# Breeze2_Power_V1.net
KiCad netlist of a schematic drawn in Altium Designer
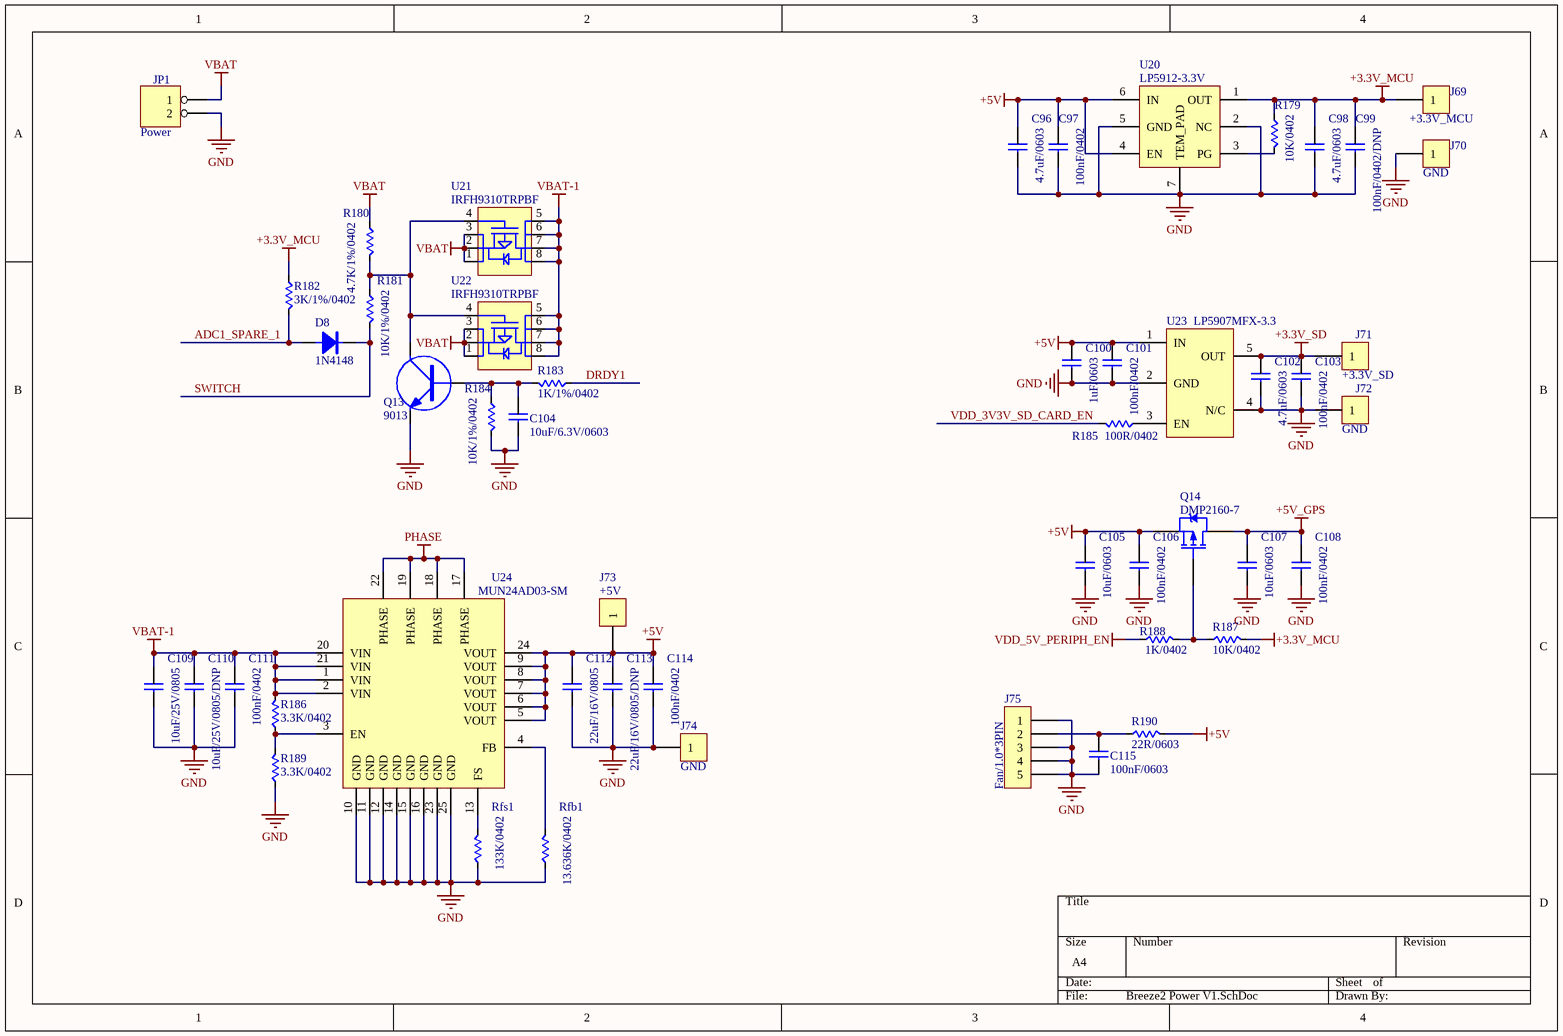
[diagram p0: Breeze2 Power V1.SchDoc]

(export (version "E")
  (design (tool "Eeschema 10.0.6"))
  (components
    (comp (ref "C96")
      (value "4.7uF/0603")
      (footprint "0603C-S")
      (description "CAP")
      (libsource (lib "YUNEEC-SCH") (part "CAP"))
    )
    (comp (ref "C97")
      (value "100nF/0402")
      (footprint "0402C-S")
      (description "CAP")
      (libsource (lib "YUNEEC-SCH") (part "CAP"))
    )
    (comp (ref "C98")
      (value "4.7uF/0603")
      (footprint "0603C-S")
      (description "CAP")
      (libsource (lib "YUNEEC-SCH") (part "CAP"))
    )
    (comp (ref "C99")
      (value "100nF/0402/DNP")
      (footprint "0402C-S")
      (description "CAP")
      (libsource (lib "YUNEEC-SCH") (part "CAP"))
    )
    (comp (ref "C100")
      (value "1uF/0603")
      (footprint "0603C-S")
      (description "CAP")
      (libsource (lib "YUNEEC-SCH") (part "CAP"))
    )
    (comp (ref "C101")
      (value "100nF/0402")
      (footprint "0402C-S")
      (description "CAP")
      (libsource (lib "YUNEEC-SCH") (part "CAP"))
    )
    (comp (ref "C102")
      (value "4.7uF/0603")
      (footprint "0603C-S")
      (description "CAP")
      (libsource (lib "YUNEEC-SCH") (part "CAP"))
    )
    (comp (ref "C103")
      (value "100nF/0402")
      (footprint "0402C-S")
      (description "CAP")
      (libsource (lib "YUNEEC-SCH") (part "CAP"))
    )
    (comp (ref "C104")
      (value "10uF/6.3V/0603")
      (footprint "0603C-S")
      (description "CAP")
      (libsource (lib "YUNEEC-SCH") (part "CAP"))
    )
    (comp (ref "C105")
      (value "10uF/0603")
      (footprint "0603C-S")
      (description "CAP")
      (libsource (lib "YUNEEC-SCH") (part "CAP"))
    )
    (comp (ref "C106")
      (value "100nF/0402")
      (footprint "0402C-S")
      (description "CAP")
      (libsource (lib "YUNEEC-SCH") (part "CAP"))
    )
    (comp (ref "C107")
      (value "10uF/0603")
      (footprint "0603C-S")
      (description "CAP")
      (libsource (lib "YUNEEC-SCH") (part "CAP"))
    )
    (comp (ref "C108")
      (value "100nF/0402")
      (footprint "0402C-S")
      (description "CAP")
      (libsource (lib "YUNEEC-SCH") (part "CAP"))
    )
    (comp (ref "C109")
      (value "10uF/25V/0805")
      (footprint "0805C-S")
      (description "CAP")
      (libsource (lib "YUNEEC-SCH") (part "CAP"))
    )
    (comp (ref "C110")
      (value "10uF/25V/0805/DNP")
      (footprint "0805C-S")
      (description "CAP")
      (libsource (lib "YUNEEC-SCH") (part "CAP"))
    )
    (comp (ref "C111")
      (value "100nF/0402")
      (footprint "0402C-S")
      (description "CAP")
      (libsource (lib "YUNEEC-SCH") (part "CAP"))
    )
    (comp (ref "C112")
      (value "22uF/16V/0805")
      (footprint "0805C-S")
      (description "CAP")
      (libsource (lib "YUNEEC-SCH") (part "CAP"))
    )
    (comp (ref "C113")
      (value "22uF/16V/0805/DNP")
      (footprint "0805C-S")
      (description "CAP")
      (libsource (lib "YUNEEC-SCH") (part "CAP"))
    )
    (comp (ref "C114")
      (value "100nF/0402")
      (footprint "0402C-S")
      (description "CAP")
      (libsource (lib "YUNEEC-SCH") (part "CAP"))
    )
    (comp (ref "C115")
      (value "100nF/0603")
      (footprint "0603C-S")
      (description "CAP")
      (libsource (lib "YUNEEC-SCH") (part "CAP"))
    )
    (comp (ref "D8")
      (value "1N4148")
      (footprint "0603D")
      (description "Diode")
      (libsource (lib "YUNEEC-SCH") (part "DIODE"))
    )
    (comp (ref "J69")
      (value "+3.3V_MCU")
      (footprint "TPJ1.0")
      (description "Connector")
      (libsource (lib "*") (part "CON1"))
    )
    (comp (ref "J70")
      (value "GND")
      (footprint "TPJ1.0")
      (description "Connector")
      (libsource (lib "YUNEEC SCH") (part "CON1"))
    )
    (comp (ref "J71")
      (value "+3.3V_SD")
      (footprint "TPJ1.0")
      (description "Connector")
      (libsource (lib "YUNEEC SCH") (part "CON1"))
    )
    (comp (ref "J72")
      (value "GND")
      (footprint "TPJ1.0")
      (description "Connector")
      (libsource (lib "YUNEEC SCH") (part "CON1"))
    )
    (comp (ref "J73")
      (value "+5V")
      (footprint "TPJ1.3")
      (description "Connector")
      (libsource (lib "") (part "CON1_1"))
    )
    (comp (ref "J74")
      (value "GND")
      (footprint "TPJ1.3")
      (description "Connector")
      (libsource (lib "YUNEEC SCH") (part "CON1"))
    )
    (comp (ref "J75")
      (value "Fan/1.0*3PIN")
      (footprint "1.0*3PIN/SMD-H")
      (description "Connector")
      (libsource (lib "YUNEEC-SCH") (part "CON5"))
    )
    (comp (ref "JP1") (value "Power") (footprint "EC2") (libsource (lib "*") (part "HEADER 2")))
    (comp (ref "Q13")
      (value "9013")
      (footprint "SOT-23A")
      (description "NPN Transistor")
      (libsource (lib "YUNEEC-SCH") (part "NPN"))
    )
    (comp (ref "Q14")
      (value "DMP2160-7")
      (footprint "SOT-23A")
      (description "HEXFET Power MOSFET")
      (libsource (lib "*") (part "IRLML6302"))
    )
    (comp (ref "R179") (value "10K/0402") (footprint "0402R-S") (libsource (lib "YUNEEC-SCH") (part "RES")))
    (comp (ref "R180")
      (value "4.7K/1%/0402")
      (footprint "0402R-S")
      (libsource (lib "YUNEEC-SCH") (part "RES"))
    )
    (comp (ref "R181")
      (value "10K/1%/0402")
      (footprint "0402R-S")
      (libsource (lib "YUNEEC-SCH") (part "RES"))
    )
    (comp (ref "R182") (value "3K/1%/0402") (footprint "0402R-S") (libsource (lib "YUNEEC-SCH") (part "RES")))
    (comp (ref "R183") (value "1K/1%/0402") (footprint "0402R-S") (libsource (lib "YUNEEC-SCH") (part "RES")))
    (comp (ref "R184")
      (value "10K/1%/0402")
      (footprint "0402R-S")
      (libsource (lib "YUNEEC-SCH") (part "RES"))
    )
    (comp (ref "R185") (value "100R/0402") (footprint "0402R-S") (libsource (lib "YUNEEC-SCH") (part "RES")))
    (comp (ref "R186")
      (value "3.3K/0402")
      (footprint "0402R-S")
      (description "Y02-00493")
      (libsource (lib "YUNEEC-SCH") (part "RES"))
    )
    (comp (ref "R187") (value "10K/0402") (footprint "0402R-S") (libsource (lib "YUNEEC-SCH") (part "RES")))
    (comp (ref "R188") (value "1K/0402") (footprint "0402R-S") (libsource (lib "YUNEEC-SCH") (part "RES")))
    (comp (ref "R189")
      (value "3.3K/0402")
      (footprint "0402R-S")
      (description "Y02-00493")
      (libsource (lib "YUNEEC-SCH") (part "RES"))
    )
    (comp (ref "R190") (value "22R/0603") (footprint "0603R-S") (libsource (lib "YUNEEC-SCH") (part "RES")))
    (comp (ref "Rfb1")
      (value "13.636K/0402")
      (footprint "0402R-S")
      (description "Y02-00493")
      (libsource (lib "YUNEEC-SCH") (part "RES"))
    )
    (comp (ref "Rfs1")
      (value "133K/0402")
      (footprint "0402R-S")
      (description "Y02-00493")
      (libsource (lib "YUNEEC-SCH") (part "RES"))
    )
    (comp (ref "U20")
      (value "LP5912-3.3V")
      (footprint "S-PWSON-N6")
      (libsource (lib "YUNEEC-SCH") (part "LP5912-3.3V"))
    )
    (comp (ref "U21")
      (value "IRFH9310TRPBF")
      (footprint "PQFN-8")
      (description "TPCC8104")
      (libsource (lib "YUNEEC-SCH") (part "TPCC8104"))
    )
    (comp (ref "U22")
      (value "IRFH9310TRPBF")
      (footprint "PQFN-8")
      (description "TPCC8104")
      (libsource (lib "YUNEEC-SCH") (part "TPCC8104"))
    )
    (comp (ref "U23")
      (value "LP5907MFX-3.3")
      (footprint "SOT-25A")
      (libsource (lib "YUNEEC-SCH") (part "LP5907"))
    )
    (comp (ref "U24")
      (value "MUN24AD03-SM")
      (footprint "MUN24AD03-SM")
      (libsource (lib "YUNEEC-SCH") (part "MUN24AD03-SM"))
    )
  )
  (nets
    (net (code "1") (name "+3.3V_MCU") (class "Default")
      (node (ref "C98") (pin "1") (pinfunction "1_1") (pintype "passive"))
      (node (ref "C99") (pin "1") (pinfunction "1_1") (pintype "passive"))
      (node (ref "J69") (pin "1") (pinfunction "1_1") (pintype "passive"))
      (node (ref "R179") (pin "1") (pinfunction "1_1") (pintype "passive"))
      (node (ref "R182") (pin "1") (pinfunction "1_1") (pintype "passive"))
      (node (ref "R187") (pin "2") (pinfunction "2_2") (pintype "passive"))
      (node (ref "U20") (pin "1") (pinfunction "OUT_1") (pintype "passive"))
    )
    (net (code "2") (name "+3.3V_SD") (class "Default")
      (node (ref "C102") (pin "1") (pinfunction "1_1") (pintype "passive"))
      (node (ref "C103") (pin "1") (pinfunction "1_1") (pintype "passive"))
      (node (ref "J71") (pin "1") (pinfunction "1_1") (pintype "passive"))
      (node (ref "U23") (pin "5") (pinfunction "OUT_5") (pintype "passive"))
    )
    (net (code "3") (name "+5V") (class "Default")
      (node (ref "C100") (pin "1") (pinfunction "1_1") (pintype "passive"))
      (node (ref "C101") (pin "1") (pinfunction "1_1") (pintype "passive"))
      (node (ref "C105") (pin "1") (pinfunction "1_1") (pintype "passive"))
      (node (ref "C106") (pin "1") (pinfunction "1_1") (pintype "passive"))
      (node (ref "C112") (pin "1") (pinfunction "1_1") (pintype "passive"))
      (node (ref "C113") (pin "1") (pinfunction "1_1") (pintype "passive"))
      (node (ref "C114") (pin "1") (pinfunction "1_1") (pintype "passive"))
      (node (ref "C96") (pin "1") (pinfunction "1_1") (pintype "passive"))
      (node (ref "C97") (pin "1") (pinfunction "1_1") (pintype "passive"))
      (node (ref "J73") (pin "1") (pinfunction "1_1") (pintype "passive"))
      (node (ref "Q14") (pin "2") (pinfunction "S_2") (pintype "passive"))
      (node (ref "R190") (pin "2") (pinfunction "2_2") (pintype "passive"))
      (node (ref "U20") (pin "4") (pinfunction "EN_4") (pintype "passive"))
      (node (ref "U20") (pin "6") (pinfunction "IN_6") (pintype "passive"))
      (node (ref "U23") (pin "1") (pinfunction "IN_1") (pintype "passive"))
      (node (ref "U24") (pin "24") (pinfunction "VOUT_24") (pintype "passive"))
      (node (ref "U24") (pin "5") (pinfunction "VOUT_5") (pintype "passive"))
      (node (ref "U24") (pin "6") (pinfunction "VOUT_6") (pintype "passive"))
      (node (ref "U24") (pin "7") (pinfunction "VOUT_7") (pintype "passive"))
      (node (ref "U24") (pin "8") (pinfunction "VOUT_8") (pintype "passive"))
      (node (ref "U24") (pin "9") (pinfunction "VOUT_9") (pintype "passive"))
    )
    (net (code "4") (name "+5V_GPS") (class "Default")
      (node (ref "C107") (pin "1") (pinfunction "1_1") (pintype "passive"))
      (node (ref "C108") (pin "1") (pinfunction "1_1") (pintype "passive"))
      (node (ref "Q14") (pin "3") (pinfunction "D_3") (pintype "passive"))
    )
    (net (code "5") (name "/ADC1_SPARE_1") (class "Default")
      (node (ref "D8") (pin "1") (pinfunction "A_1") (pintype "passive"))
      (node (ref "R182") (pin "2") (pinfunction "2_2") (pintype "passive"))
    )
    (net (code "6") (name "/DRDY1") (class "Default")
      (node (ref "R183") (pin "1") (pinfunction "1_1") (pintype "passive"))
    )
    (net (code "7") (name "/SWITCH") (class "Default")
      (node (ref "D8") (pin "2") (pinfunction "K_2") (pintype "passive"))
      (node (ref "R181") (pin "2") (pinfunction "2_2") (pintype "passive"))
    )
    (net (code "8") (name "/VDD_3V3V_SD_CARD_EN") (class "Default")
      (node (ref "R185") (pin "2") (pinfunction "2_2") (pintype "passive"))
    )
    (net (code "9") (name "GND") (class "Default")
      (node (ref "C100") (pin "2") (pinfunction "2_2") (pintype "passive"))
      (node (ref "C101") (pin "2") (pinfunction "2_2") (pintype "passive"))
      (node (ref "C102") (pin "2") (pinfunction "2_2") (pintype "passive"))
      (node (ref "C103") (pin "2") (pinfunction "2_2") (pintype "passive"))
      (node (ref "C104") (pin "2") (pinfunction "2_2") (pintype "passive"))
      (node (ref "C105") (pin "2") (pinfunction "2_2") (pintype "passive"))
      (node (ref "C106") (pin "2") (pinfunction "2_2") (pintype "passive"))
      (node (ref "C107") (pin "2") (pinfunction "2_2") (pintype "passive"))
      (node (ref "C108") (pin "2") (pinfunction "2_2") (pintype "passive"))
      (node (ref "C109") (pin "2") (pinfunction "2_2") (pintype "passive"))
      (node (ref "C110") (pin "2") (pinfunction "2_2") (pintype "passive"))
      (node (ref "C111") (pin "2") (pinfunction "2_2") (pintype "passive"))
      (node (ref "C112") (pin "2") (pinfunction "2_2") (pintype "passive"))
      (node (ref "C113") (pin "2") (pinfunction "2_2") (pintype "passive"))
      (node (ref "C114") (pin "2") (pinfunction "2_2") (pintype "passive"))
      (node (ref "C115") (pin "2") (pinfunction "2_2") (pintype "passive"))
      (node (ref "C96") (pin "2") (pinfunction "2_2") (pintype "passive"))
      (node (ref "C97") (pin "2") (pinfunction "2_2") (pintype "passive"))
      (node (ref "C98") (pin "2") (pinfunction "2_2") (pintype "passive"))
      (node (ref "C99") (pin "2") (pinfunction "2_2") (pintype "passive"))
      (node (ref "J70") (pin "1") (pinfunction "1_1") (pintype "passive"))
      (node (ref "J72") (pin "1") (pinfunction "1_1") (pintype "passive"))
      (node (ref "J74") (pin "1") (pinfunction "1_1") (pintype "passive"))
      (node (ref "J75") (pin "1") (pinfunction "1_1") (pintype "passive"))
      (node (ref "J75") (pin "3") (pinfunction "3_3") (pintype "passive"))
      (node (ref "J75") (pin "4") (pinfunction "4_4") (pintype "passive"))
      (node (ref "J75") (pin "5") (pinfunction "5_5") (pintype "passive"))
      (node (ref "JP1") (pin "2") (pinfunction "2_2") (pintype "passive"))
      (node (ref "Q13") (pin "2") (pinfunction "E_2") (pintype "passive"))
      (node (ref "R184") (pin "2") (pinfunction "2_2") (pintype "passive"))
      (node (ref "R189") (pin "1") (pinfunction "1_1") (pintype "passive"))
      (node (ref "Rfb1") (pin "1") (pinfunction "1_1") (pintype "passive"))
      (node (ref "Rfs1") (pin "1") (pinfunction "1_1") (pintype "passive"))
      (node (ref "U20") (pin "2") (pinfunction "NC_2") (pintype "passive"))
      (node (ref "U20") (pin "5") (pinfunction "GND_5") (pintype "passive"))
      (node (ref "U20") (pin "7") (pinfunction "TEM_PAD_7") (pintype "passive"))
      (node (ref "U23") (pin "2") (pinfunction "GND_2") (pintype "passive"))
      (node (ref "U23") (pin "4") (pinfunction "N/C_4") (pintype "passive"))
      (node (ref "U24") (pin "10") (pinfunction "GND_10") (pintype "passive"))
      (node (ref "U24") (pin "11") (pinfunction "GND_11") (pintype "passive"))
      (node (ref "U24") (pin "12") (pinfunction "GND_12") (pintype "passive"))
      (node (ref "U24") (pin "14") (pinfunction "GND_14") (pintype "passive"))
      (node (ref "U24") (pin "15") (pinfunction "GND_15") (pintype "passive"))
      (node (ref "U24") (pin "16") (pinfunction "GND_16") (pintype "passive"))
      (node (ref "U24") (pin "23") (pinfunction "GND_23") (pintype "passive"))
      (node (ref "U24") (pin "25") (pinfunction "GND_25") (pintype "passive"))
    )
    (net (code "10") (name "Net-(C115-Pad1)") (class "Default")
      (node (ref "C115") (pin "1") (pinfunction "1_1") (pintype "passive"))
      (node (ref "J75") (pin "2") (pinfunction "2_2") (pintype "passive"))
      (node (ref "R190") (pin "1") (pinfunction "1_1") (pintype "passive"))
    )
    (net (code "11") (name "Net-(Q13-B)") (class "Default")
      (node (ref "C104") (pin "1") (pinfunction "1_1") (pintype "passive"))
      (node (ref "Q13") (pin "1") (pinfunction "B_1") (pintype "passive"))
      (node (ref "R183") (pin "2") (pinfunction "2_2") (pintype "passive"))
      (node (ref "R184") (pin "1") (pinfunction "1_1") (pintype "passive"))
    )
    (net (code "12") (name "Net-(Q13-C)") (class "Default")
      (node (ref "Q13") (pin "3") (pinfunction "C_3") (pintype "passive"))
      (node (ref "R180") (pin "2") (pinfunction "2_2") (pintype "passive"))
      (node (ref "R181") (pin "1") (pinfunction "1_1") (pintype "passive"))
      (node (ref "U21") (pin "4") (pinfunction "GATE_4") (pintype "passive"))
      (node (ref "U22") (pin "4") (pinfunction "GATE_4") (pintype "passive"))
    )
    (net (code "13") (name "Net-(Q14-G)") (class "Default")
      (node (ref "Q14") (pin "1") (pinfunction "G_1") (pintype "passive"))
      (node (ref "R187") (pin "1") (pinfunction "1_1") (pintype "passive"))
      (node (ref "R188") (pin "2") (pinfunction "2_2") (pintype "passive"))
    )
    (net (code "14") (name "Net-(U20-PG)") (class "Default")
      (node (ref "R179") (pin "2") (pinfunction "2_2") (pintype "passive"))
      (node (ref "U20") (pin "3") (pinfunction "PG_3") (pintype "passive"))
    )
    (net (code "15") (name "Net-(U23-EN)") (class "Default")
      (node (ref "R185") (pin "1") (pinfunction "1_1") (pintype "passive"))
      (node (ref "U23") (pin "3") (pinfunction "EN_3") (pintype "passive"))
    )
    (net (code "16") (name "Net-(U24-EN)") (class "Default")
      (node (ref "R186") (pin "1") (pinfunction "1_1") (pintype "passive"))
      (node (ref "R189") (pin "2") (pinfunction "2_2") (pintype "passive"))
      (node (ref "U24") (pin "3") (pinfunction "EN_3") (pintype "passive"))
    )
    (net (code "17") (name "Net-(U24-FB)") (class "Default")
      (node (ref "Rfb1") (pin "2") (pinfunction "2_2") (pintype "passive"))
      (node (ref "U24") (pin "4") (pinfunction "FB_4") (pintype "passive"))
    )
    (net (code "18") (name "Net-(U24-FS)") (class "Default")
      (node (ref "Rfs1") (pin "2") (pinfunction "2_2") (pintype "passive"))
      (node (ref "U24") (pin "13") (pinfunction "FS_13") (pintype "passive"))
    )
    (net (code "19") (name "PHASE") (class "Default")
      (node (ref "U24") (pin "17") (pinfunction "PHASE_17") (pintype "passive"))
      (node (ref "U24") (pin "18") (pinfunction "PHASE_18") (pintype "passive"))
      (node (ref "U24") (pin "19") (pinfunction "PHASE_19") (pintype "passive"))
      (node (ref "U24") (pin "22") (pinfunction "PHASE_22") (pintype "passive"))
    )
    (net (code "20") (name "VBAT") (class "Default")
      (node (ref "JP1") (pin "1") (pinfunction "1_1") (pintype "passive"))
      (node (ref "R180") (pin "1") (pinfunction "1_1") (pintype "passive"))
      (node (ref "U21") (pin "1") (pinfunction "1_1") (pintype "passive"))
      (node (ref "U21") (pin "2") (pinfunction "2_2") (pintype "passive"))
      (node (ref "U21") (pin "3") (pinfunction "SOURCE_3") (pintype "passive"))
      (node (ref "U22") (pin "1") (pinfunction "1_1") (pintype "passive"))
      (node (ref "U22") (pin "2") (pinfunction "2_2") (pintype "passive"))
      (node (ref "U22") (pin "3") (pinfunction "SOURCE_3") (pintype "passive"))
    )
    (net (code "21") (name "VBAT-1") (class "Default")
      (node (ref "C109") (pin "1") (pinfunction "1_1") (pintype "passive"))
      (node (ref "C110") (pin "1") (pinfunction "1_1") (pintype "passive"))
      (node (ref "C111") (pin "1") (pinfunction "1_1") (pintype "passive"))
      (node (ref "R186") (pin "2") (pinfunction "2_2") (pintype "passive"))
      (node (ref "U21") (pin "5") (pinfunction "5_5") (pintype "passive"))
      (node (ref "U21") (pin "6") (pinfunction "6_6") (pintype "passive"))
      (node (ref "U21") (pin "7") (pinfunction "DRAIN_7") (pintype "passive"))
      (node (ref "U21") (pin "8") (pinfunction "3_8") (pintype "passive"))
      (node (ref "U22") (pin "5") (pinfunction "5_5") (pintype "passive"))
      (node (ref "U22") (pin "6") (pinfunction "6_6") (pintype "passive"))
      (node (ref "U22") (pin "7") (pinfunction "DRAIN_7") (pintype "passive"))
      (node (ref "U22") (pin "8") (pinfunction "3_8") (pintype "passive"))
      (node (ref "U24") (pin "1") (pinfunction "VIN_1") (pintype "passive"))
      (node (ref "U24") (pin "2") (pinfunction "VIN_2") (pintype "passive"))
      (node (ref "U24") (pin "20") (pinfunction "VIN_20") (pintype "passive"))
      (node (ref "U24") (pin "21") (pinfunction "VIN_21") (pintype "passive"))
    )
    (net (code "22") (name "VDD_5V_PERIPH_EN") (class "Default")
      (node (ref "R188") (pin "1") (pinfunction "1_1") (pintype "passive"))
    )
  )
)
